# tappytap_6x6_connopposite.net
KiCad netlist of a schematic drawn in EAGLE
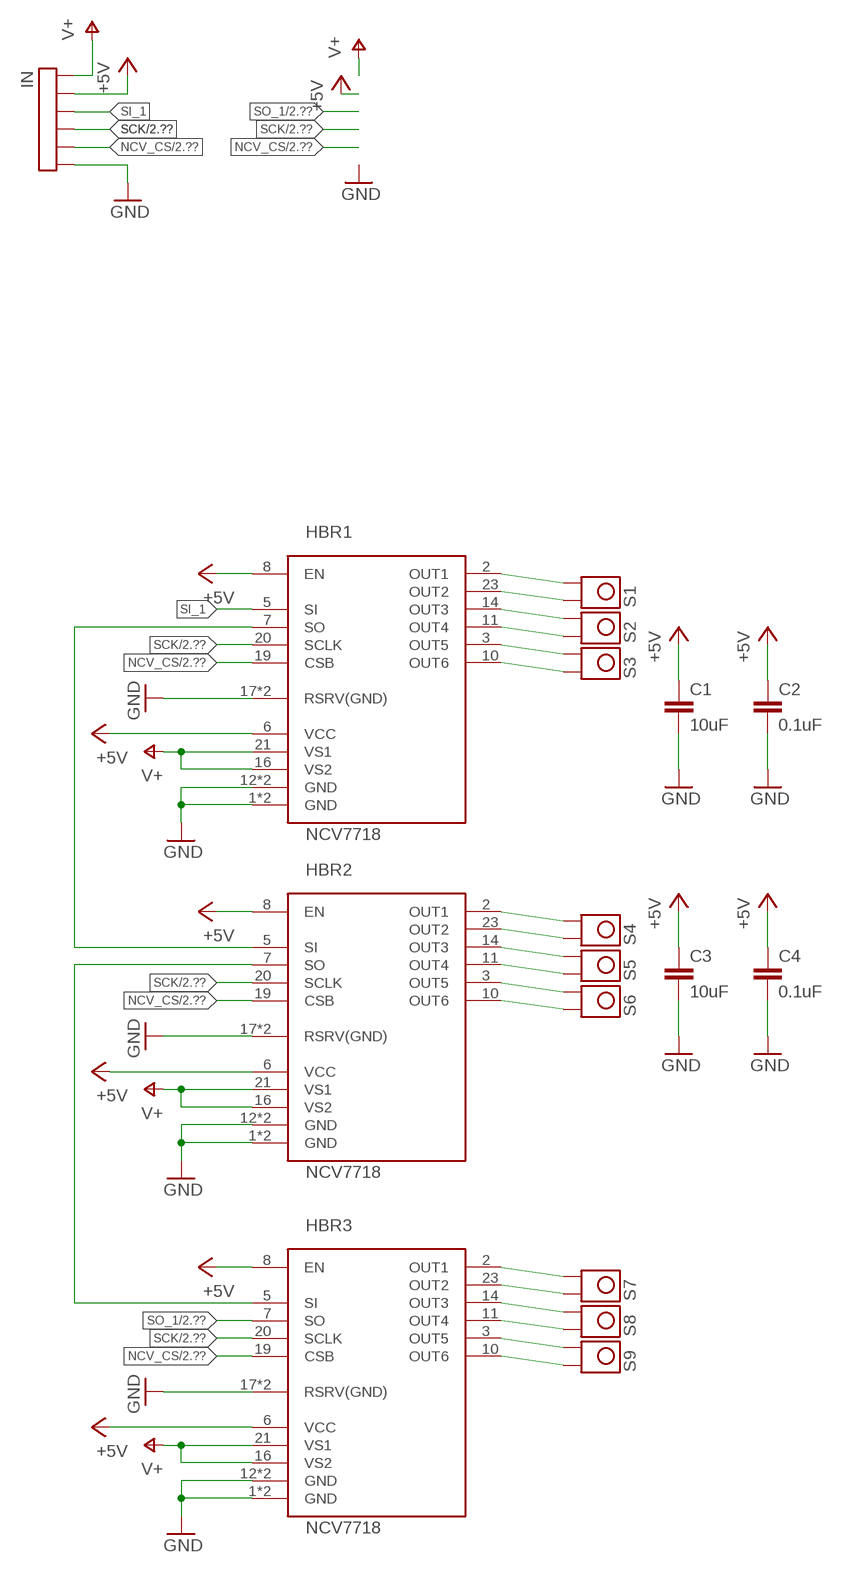
[diagram p0: schematic, sheet 1]
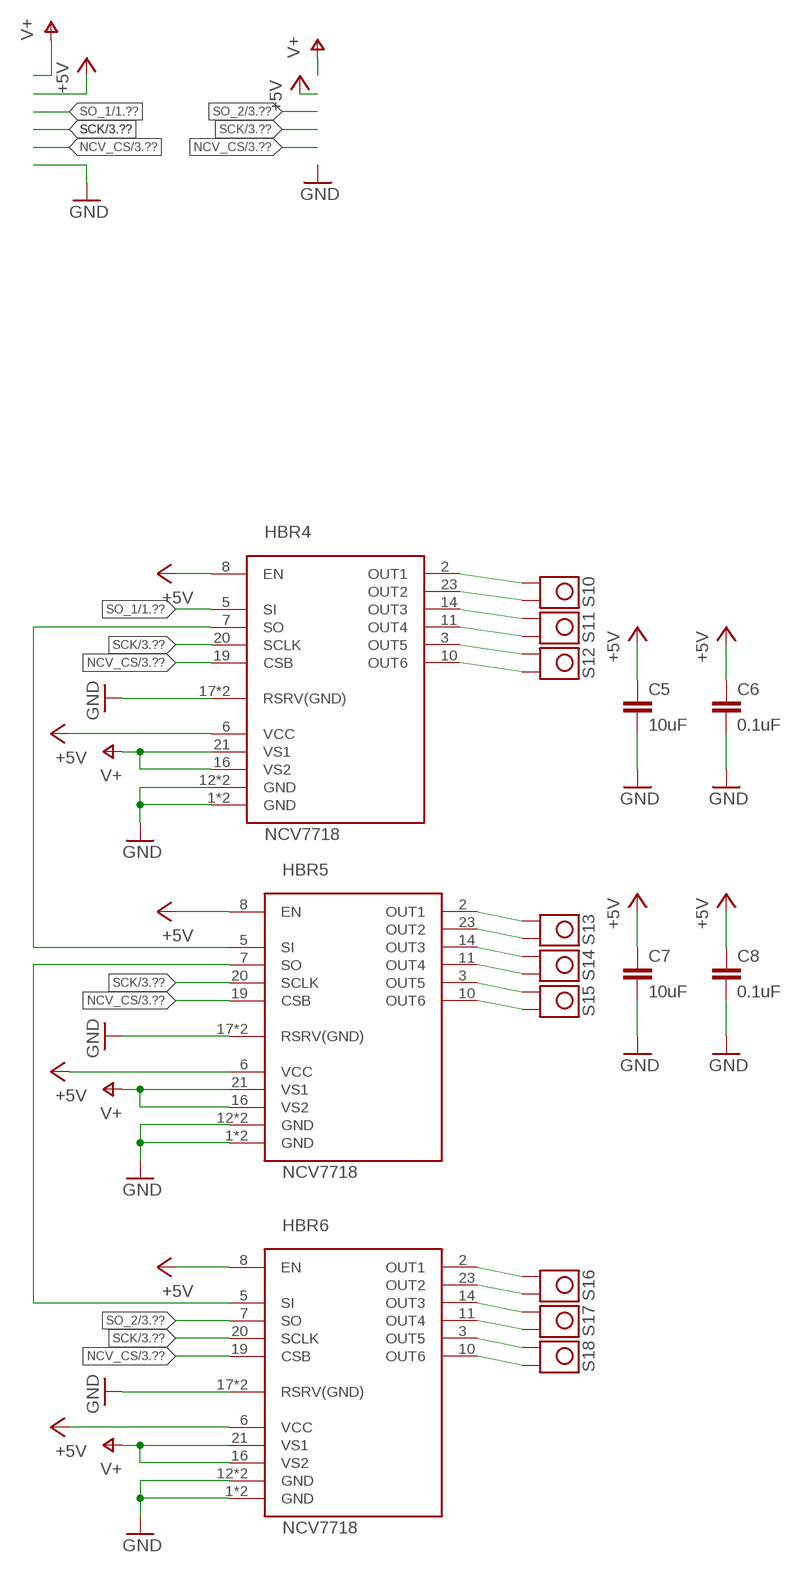
[diagram p1: schematic, sheet 2]
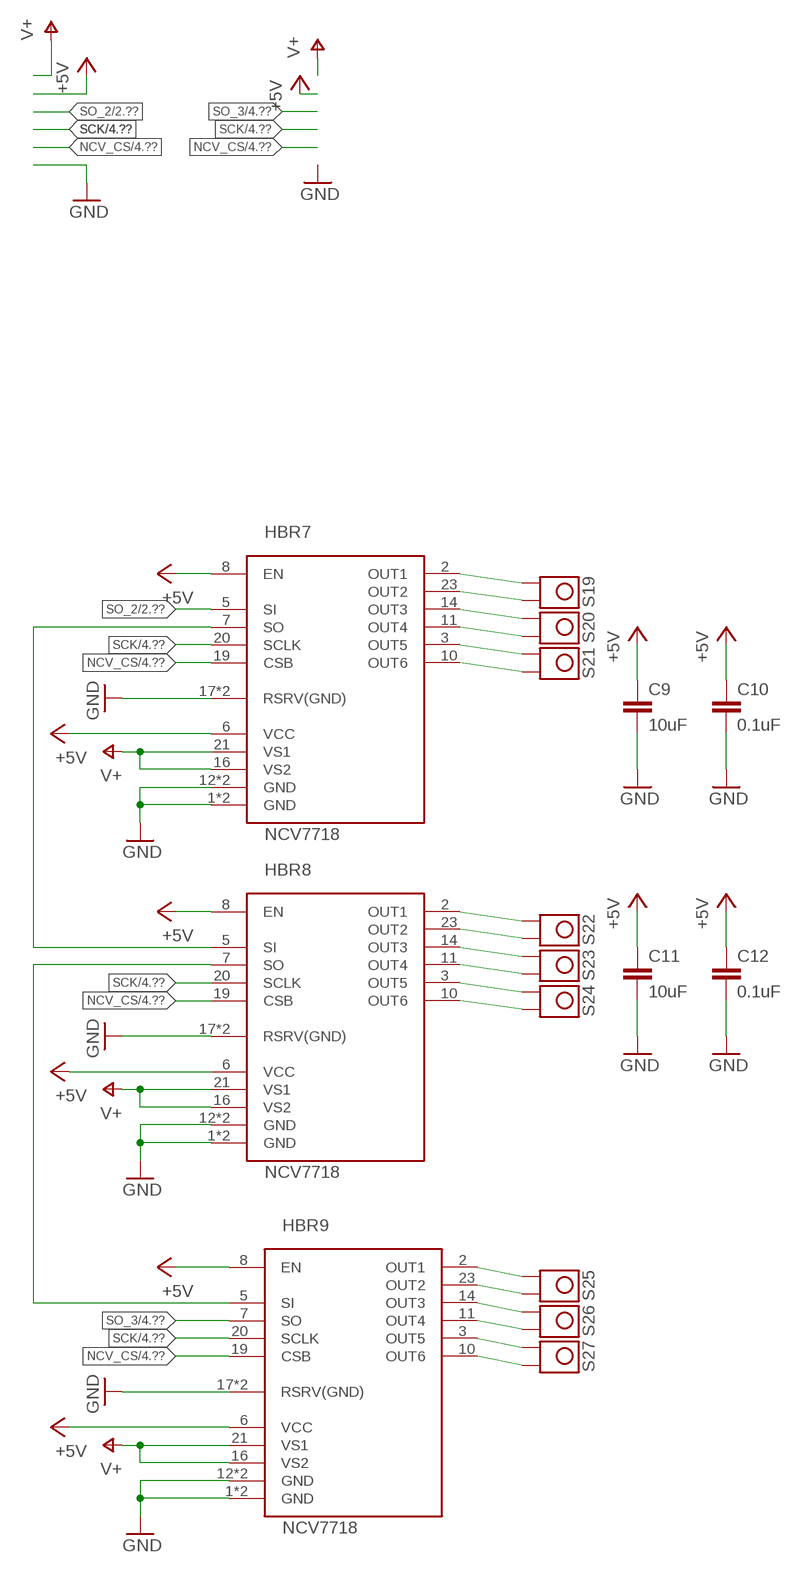
[diagram p2: schematic, sheet 3]
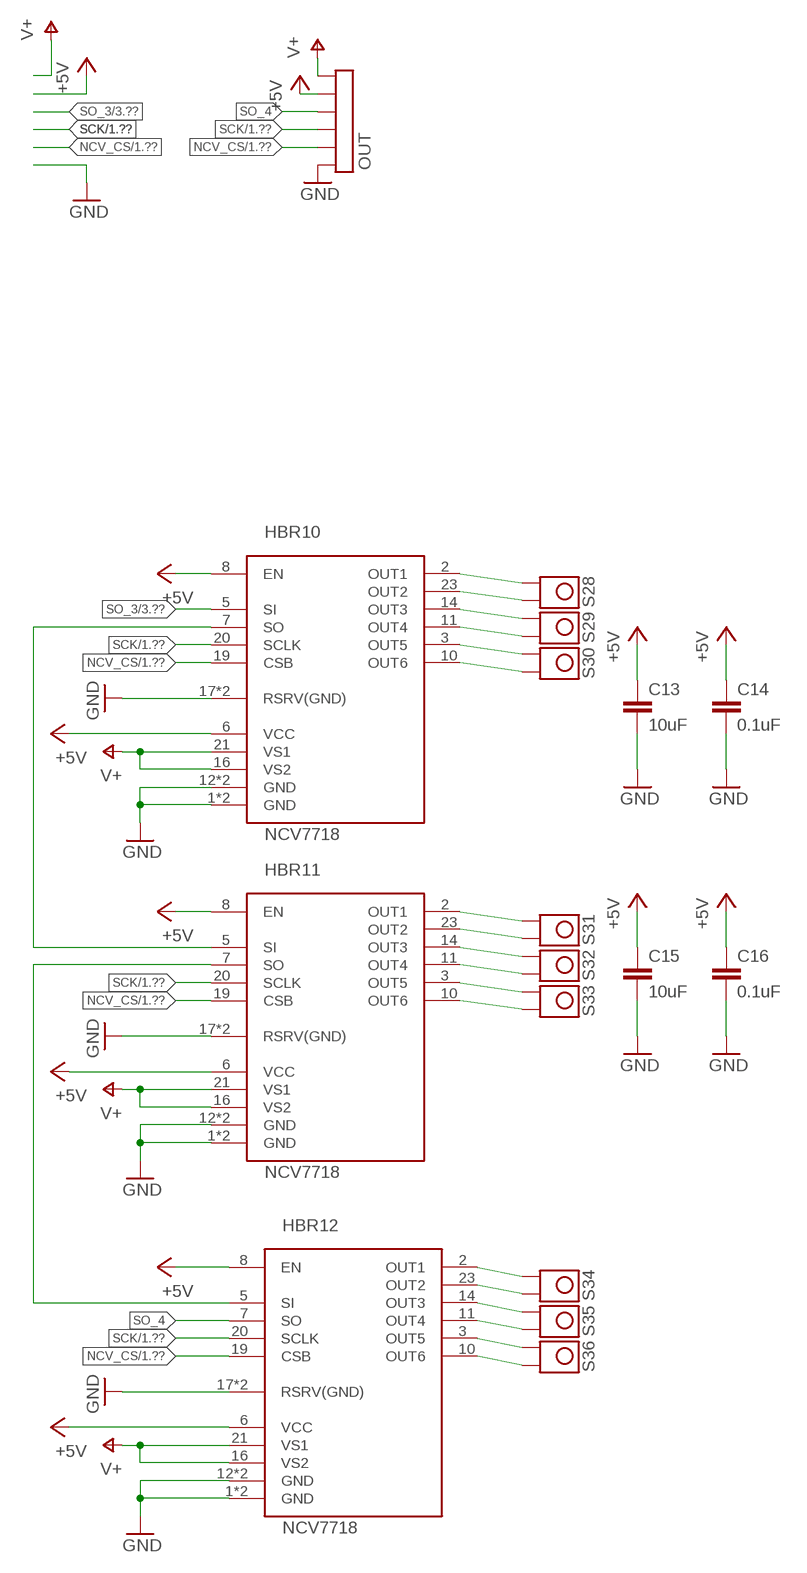
[diagram p3: schematic, sheet 4]

(export (version "E")
  (design (tool "Eeschema 10.0.6"))
  (components
    (comp (ref "C13")
      (value "10uF")
      (footprint "eagle-import:C0603")
      (libsource (lib "eagle-import") (part "C-EUC0603"))
    )
    (comp (ref "C14")
      (value "0.1uF")
      (footprint "eagle-import:C0603")
      (libsource (lib "eagle-import") (part "C-EUC0603"))
    )
    (comp (ref "C15")
      (value "10uF")
      (footprint "eagle-import:C0603")
      (libsource (lib "eagle-import") (part "C-EUC0603"))
    )
    (comp (ref "C16")
      (value "0.1uF")
      (footprint "eagle-import:C0603")
      (libsource (lib "eagle-import") (part "C-EUC0603"))
    )
    (comp (ref "HBR10")
      (value "NCV7718")
      (footprint "eagle-import:SSOP-24")
      (libsource (lib "eagle-import") (part "NCV7718"))
    )
    (comp (ref "HBR11")
      (value "NCV7718")
      (footprint "eagle-import:SSOP-24")
      (libsource (lib "eagle-import") (part "NCV7718"))
    )
    (comp (ref "HBR12")
      (value "NCV7718")
      (footprint "eagle-import:SSOP-24")
      (libsource (lib "eagle-import") (part "NCV7718"))
    )
    (comp (ref "OUT")
      (value "TP6")
      (footprint "eagle-import:TP6_2MM")
      (libsource (lib "eagle-import") (part "TP6"))
    )
    (comp (ref "S28")
      (value "TP_6MM_BIG_PAD")
      (footprint "eagle-import:TP_6MM_BIG_PAD")
      (libsource (lib "eagle-import") (part "TP_6MM_BIG_PAD"))
    )
    (comp (ref "S29")
      (value "TP_6MM_BIG_PAD")
      (footprint "eagle-import:TP_6MM_BIG_PAD")
      (libsource (lib "eagle-import") (part "TP_6MM_BIG_PAD"))
    )
    (comp (ref "S30")
      (value "TP_6MM_BIG_PAD")
      (footprint "eagle-import:TP_6MM_BIG_PAD")
      (libsource (lib "eagle-import") (part "TP_6MM_BIG_PAD"))
    )
    (comp (ref "S31")
      (value "TP_6MM_BIG_PAD")
      (footprint "eagle-import:TP_6MM_BIG_PAD")
      (libsource (lib "eagle-import") (part "TP_6MM_BIG_PAD"))
    )
    (comp (ref "S32")
      (value "TP_6MM_BIG_PAD")
      (footprint "eagle-import:TP_6MM_BIG_PAD")
      (libsource (lib "eagle-import") (part "TP_6MM_BIG_PAD"))
    )
    (comp (ref "S33")
      (value "TP_6MM_BIG_PAD")
      (footprint "eagle-import:TP_6MM_BIG_PAD")
      (libsource (lib "eagle-import") (part "TP_6MM_BIG_PAD"))
    )
    (comp (ref "S34")
      (value "TP_6MM_BIG_PAD")
      (footprint "eagle-import:TP_6MM_BIG_PAD")
      (libsource (lib "eagle-import") (part "TP_6MM_BIG_PAD"))
    )
    (comp (ref "S35")
      (value "TP_6MM_BIG_PAD")
      (footprint "eagle-import:TP_6MM_BIG_PAD")
      (libsource (lib "eagle-import") (part "TP_6MM_BIG_PAD"))
    )
    (comp (ref "S36")
      (value "TP_6MM_BIG_PAD")
      (footprint "eagle-import:TP_6MM_BIG_PAD")
      (libsource (lib "eagle-import") (part "TP_6MM_BIG_PAD"))
    )
    (comp (ref "C9")
      (value "10uF")
      (footprint "eagle-import:C0603")
      (libsource (lib "eagle-import") (part "C-EUC0603"))
    )
    (comp (ref "C10")
      (value "0.1uF")
      (footprint "eagle-import:C0603")
      (libsource (lib "eagle-import") (part "C-EUC0603"))
    )
    (comp (ref "C11")
      (value "10uF")
      (footprint "eagle-import:C0603")
      (libsource (lib "eagle-import") (part "C-EUC0603"))
    )
    (comp (ref "C12")
      (value "0.1uF")
      (footprint "eagle-import:C0603")
      (libsource (lib "eagle-import") (part "C-EUC0603"))
    )
    (comp (ref "HBR7")
      (value "NCV7718")
      (footprint "eagle-import:SSOP-24")
      (libsource (lib "eagle-import") (part "NCV7718"))
    )
    (comp (ref "HBR8")
      (value "NCV7718")
      (footprint "eagle-import:SSOP-24")
      (libsource (lib "eagle-import") (part "NCV7718"))
    )
    (comp (ref "HBR9")
      (value "NCV7718")
      (footprint "eagle-import:SSOP-24")
      (libsource (lib "eagle-import") (part "NCV7718"))
    )
    (comp (ref "S19")
      (value "TP_6MM_BIG_PAD")
      (footprint "eagle-import:TP_6MM_BIG_PAD")
      (libsource (lib "eagle-import") (part "TP_6MM_BIG_PAD"))
    )
    (comp (ref "S20")
      (value "TP_6MM_BIG_PAD")
      (footprint "eagle-import:TP_6MM_BIG_PAD")
      (libsource (lib "eagle-import") (part "TP_6MM_BIG_PAD"))
    )
    (comp (ref "S21")
      (value "TP_6MM_BIG_PAD")
      (footprint "eagle-import:TP_6MM_BIG_PAD")
      (libsource (lib "eagle-import") (part "TP_6MM_BIG_PAD"))
    )
    (comp (ref "S22")
      (value "TP_6MM_BIG_PAD")
      (footprint "eagle-import:TP_6MM_BIG_PAD")
      (libsource (lib "eagle-import") (part "TP_6MM_BIG_PAD"))
    )
    (comp (ref "S23")
      (value "TP_6MM_BIG_PAD")
      (footprint "eagle-import:TP_6MM_BIG_PAD")
      (libsource (lib "eagle-import") (part "TP_6MM_BIG_PAD"))
    )
    (comp (ref "S24")
      (value "TP_6MM_BIG_PAD")
      (footprint "eagle-import:TP_6MM_BIG_PAD")
      (libsource (lib "eagle-import") (part "TP_6MM_BIG_PAD"))
    )
    (comp (ref "S25")
      (value "TP_6MM_BIG_PAD")
      (footprint "eagle-import:TP_6MM_BIG_PAD")
      (libsource (lib "eagle-import") (part "TP_6MM_BIG_PAD"))
    )
    (comp (ref "S26")
      (value "TP_6MM_BIG_PAD")
      (footprint "eagle-import:TP_6MM_BIG_PAD")
      (libsource (lib "eagle-import") (part "TP_6MM_BIG_PAD"))
    )
    (comp (ref "S27")
      (value "TP_6MM_BIG_PAD")
      (footprint "eagle-import:TP_6MM_BIG_PAD")
      (libsource (lib "eagle-import") (part "TP_6MM_BIG_PAD"))
    )
    (comp (ref "C1")
      (value "10uF")
      (footprint "eagle-import:C0603")
      (libsource (lib "eagle-import") (part "C-EUC0603"))
    )
    (comp (ref "C2")
      (value "0.1uF")
      (footprint "eagle-import:C0603")
      (libsource (lib "eagle-import") (part "C-EUC0603"))
    )
    (comp (ref "C3")
      (value "10uF")
      (footprint "eagle-import:C0603")
      (libsource (lib "eagle-import") (part "C-EUC0603"))
    )
    (comp (ref "C4")
      (value "0.1uF")
      (footprint "eagle-import:C0603")
      (libsource (lib "eagle-import") (part "C-EUC0603"))
    )
    (comp (ref "HBR1")
      (value "NCV7718")
      (footprint "eagle-import:SSOP-24")
      (libsource (lib "eagle-import") (part "NCV7718"))
    )
    (comp (ref "HBR2")
      (value "NCV7718")
      (footprint "eagle-import:SSOP-24")
      (libsource (lib "eagle-import") (part "NCV7718"))
    )
    (comp (ref "HBR3")
      (value "NCV7718")
      (footprint "eagle-import:SSOP-24")
      (libsource (lib "eagle-import") (part "NCV7718"))
    )
    (comp (ref "IN")
      (value "TP6")
      (footprint "eagle-import:TP6_2MM")
      (libsource (lib "eagle-import") (part "TP6"))
    )
    (comp (ref "S1")
      (value "TP_6MM_BIG_PAD")
      (footprint "eagle-import:TP_6MM_BIG_PAD")
      (libsource (lib "eagle-import") (part "TP_6MM_BIG_PAD"))
    )
    (comp (ref "S2")
      (value "TP_6MM_BIG_PAD")
      (footprint "eagle-import:TP_6MM_BIG_PAD")
      (libsource (lib "eagle-import") (part "TP_6MM_BIG_PAD"))
    )
    (comp (ref "S3")
      (value "TP_6MM_BIG_PAD")
      (footprint "eagle-import:TP_6MM_BIG_PAD")
      (libsource (lib "eagle-import") (part "TP_6MM_BIG_PAD"))
    )
    (comp (ref "S4")
      (value "TP_6MM_BIG_PAD")
      (footprint "eagle-import:TP_6MM_BIG_PAD")
      (libsource (lib "eagle-import") (part "TP_6MM_BIG_PAD"))
    )
    (comp (ref "S5")
      (value "TP_6MM_BIG_PAD")
      (footprint "eagle-import:TP_6MM_BIG_PAD")
      (libsource (lib "eagle-import") (part "TP_6MM_BIG_PAD"))
    )
    (comp (ref "S6")
      (value "TP_6MM_BIG_PAD")
      (footprint "eagle-import:TP_6MM_BIG_PAD")
      (libsource (lib "eagle-import") (part "TP_6MM_BIG_PAD"))
    )
    (comp (ref "S7")
      (value "TP_6MM_BIG_PAD")
      (footprint "eagle-import:TP_6MM_BIG_PAD")
      (libsource (lib "eagle-import") (part "TP_6MM_BIG_PAD"))
    )
    (comp (ref "S8")
      (value "TP_6MM_BIG_PAD")
      (footprint "eagle-import:TP_6MM_BIG_PAD")
      (libsource (lib "eagle-import") (part "TP_6MM_BIG_PAD"))
    )
    (comp (ref "S9")
      (value "TP_6MM_BIG_PAD")
      (footprint "eagle-import:TP_6MM_BIG_PAD")
      (libsource (lib "eagle-import") (part "TP_6MM_BIG_PAD"))
    )
    (comp (ref "C5")
      (value "10uF")
      (footprint "eagle-import:C0603")
      (libsource (lib "eagle-import") (part "C-EUC0603"))
    )
    (comp (ref "C6")
      (value "0.1uF")
      (footprint "eagle-import:C0603")
      (libsource (lib "eagle-import") (part "C-EUC0603"))
    )
    (comp (ref "C7")
      (value "10uF")
      (footprint "eagle-import:C0603")
      (libsource (lib "eagle-import") (part "C-EUC0603"))
    )
    (comp (ref "C8")
      (value "0.1uF")
      (footprint "eagle-import:C0603")
      (libsource (lib "eagle-import") (part "C-EUC0603"))
    )
    (comp (ref "HBR4")
      (value "NCV7718")
      (footprint "eagle-import:SSOP-24")
      (libsource (lib "eagle-import") (part "NCV7718"))
    )
    (comp (ref "HBR5")
      (value "NCV7718")
      (footprint "eagle-import:SSOP-24")
      (libsource (lib "eagle-import") (part "NCV7718"))
    )
    (comp (ref "HBR6")
      (value "NCV7718")
      (footprint "eagle-import:SSOP-24")
      (libsource (lib "eagle-import") (part "NCV7718"))
    )
    (comp (ref "S10")
      (value "TP_6MM_BIG_PAD")
      (footprint "eagle-import:TP_6MM_BIG_PAD")
      (libsource (lib "eagle-import") (part "TP_6MM_BIG_PAD"))
    )
    (comp (ref "S11")
      (value "TP_6MM_BIG_PAD")
      (footprint "eagle-import:TP_6MM_BIG_PAD")
      (libsource (lib "eagle-import") (part "TP_6MM_BIG_PAD"))
    )
    (comp (ref "S12")
      (value "TP_6MM_BIG_PAD")
      (footprint "eagle-import:TP_6MM_BIG_PAD")
      (libsource (lib "eagle-import") (part "TP_6MM_BIG_PAD"))
    )
    (comp (ref "S13")
      (value "TP_6MM_BIG_PAD")
      (footprint "eagle-import:TP_6MM_BIG_PAD")
      (libsource (lib "eagle-import") (part "TP_6MM_BIG_PAD"))
    )
    (comp (ref "S14")
      (value "TP_6MM_BIG_PAD")
      (footprint "eagle-import:TP_6MM_BIG_PAD")
      (libsource (lib "eagle-import") (part "TP_6MM_BIG_PAD"))
    )
    (comp (ref "S15")
      (value "TP_6MM_BIG_PAD")
      (footprint "eagle-import:TP_6MM_BIG_PAD")
      (libsource (lib "eagle-import") (part "TP_6MM_BIG_PAD"))
    )
    (comp (ref "S16")
      (value "TP_6MM_BIG_PAD")
      (footprint "eagle-import:TP_6MM_BIG_PAD")
      (libsource (lib "eagle-import") (part "TP_6MM_BIG_PAD"))
    )
    (comp (ref "S17")
      (value "TP_6MM_BIG_PAD")
      (footprint "eagle-import:TP_6MM_BIG_PAD")
      (libsource (lib "eagle-import") (part "TP_6MM_BIG_PAD"))
    )
    (comp (ref "S18")
      (value "TP_6MM_BIG_PAD")
      (footprint "eagle-import:TP_6MM_BIG_PAD")
      (libsource (lib "eagle-import") (part "TP_6MM_BIG_PAD"))
    )
  )
  (nets
    (net (code "1") (name "+5V") (class "Default")
      (node (ref "C1") (pin "1") (pinfunction "1_1") (pintype "passive"))
      (node (ref "C10") (pin "1") (pinfunction "1_1") (pintype "passive"))
      (node (ref "C11") (pin "1") (pinfunction "1_1") (pintype "passive"))
      (node (ref "C12") (pin "1") (pinfunction "1_1") (pintype "passive"))
      (node (ref "C13") (pin "1") (pinfunction "1_1") (pintype "passive"))
      (node (ref "C14") (pin "1") (pinfunction "1_1") (pintype "passive"))
      (node (ref "C15") (pin "1") (pinfunction "1_1") (pintype "passive"))
      (node (ref "C16") (pin "1") (pinfunction "1_1") (pintype "passive"))
      (node (ref "C2") (pin "1") (pinfunction "1_1") (pintype "passive"))
      (node (ref "C3") (pin "1") (pinfunction "1_1") (pintype "passive"))
      (node (ref "C4") (pin "1") (pinfunction "1_1") (pintype "passive"))
      (node (ref "C5") (pin "1") (pinfunction "1_1") (pintype "passive"))
      (node (ref "C6") (pin "1") (pinfunction "1_1") (pintype "passive"))
      (node (ref "C7") (pin "1") (pinfunction "1_1") (pintype "passive"))
      (node (ref "C8") (pin "1") (pinfunction "1_1") (pintype "passive"))
      (node (ref "C9") (pin "1") (pinfunction "1_1") (pintype "passive"))
      (node (ref "HBR1") (pin "6") (pinfunction "VCC_6") (pintype "bidirectional"))
      (node (ref "HBR1") (pin "8") (pinfunction "EN_8") (pintype "bidirectional"))
      (node (ref "HBR10") (pin "6") (pinfunction "VCC_6") (pintype "bidirectional"))
      (node (ref "HBR10") (pin "8") (pinfunction "EN_8") (pintype "bidirectional"))
      (node (ref "HBR11") (pin "6") (pinfunction "VCC_6") (pintype "bidirectional"))
      (node (ref "HBR11") (pin "8") (pinfunction "EN_8") (pintype "bidirectional"))
      (node (ref "HBR12") (pin "6") (pinfunction "VCC_6") (pintype "bidirectional"))
      (node (ref "HBR12") (pin "8") (pinfunction "EN_8") (pintype "bidirectional"))
      (node (ref "HBR2") (pin "6") (pinfunction "VCC_6") (pintype "bidirectional"))
      (node (ref "HBR2") (pin "8") (pinfunction "EN_8") (pintype "bidirectional"))
      (node (ref "HBR3") (pin "6") (pinfunction "VCC_6") (pintype "bidirectional"))
      (node (ref "HBR3") (pin "8") (pinfunction "EN_8") (pintype "bidirectional"))
      (node (ref "HBR4") (pin "6") (pinfunction "VCC_6") (pintype "bidirectional"))
      (node (ref "HBR4") (pin "8") (pinfunction "EN_8") (pintype "bidirectional"))
      (node (ref "HBR5") (pin "6") (pinfunction "VCC_6") (pintype "bidirectional"))
      (node (ref "HBR5") (pin "8") (pinfunction "EN_8") (pintype "bidirectional"))
      (node (ref "HBR6") (pin "6") (pinfunction "VCC_6") (pintype "bidirectional"))
      (node (ref "HBR6") (pin "8") (pinfunction "EN_8") (pintype "bidirectional"))
      (node (ref "HBR7") (pin "6") (pinfunction "VCC_6") (pintype "bidirectional"))
      (node (ref "HBR7") (pin "8") (pinfunction "EN_8") (pintype "bidirectional"))
      (node (ref "HBR8") (pin "6") (pinfunction "VCC_6") (pintype "bidirectional"))
      (node (ref "HBR8") (pin "8") (pinfunction "EN_8") (pintype "bidirectional"))
      (node (ref "HBR9") (pin "6") (pinfunction "VCC_6") (pintype "bidirectional"))
      (node (ref "HBR9") (pin "8") (pinfunction "EN_8") (pintype "bidirectional"))
      (node (ref "IN") (pin "P$5") (pinfunction "5_P$5") (pintype "bidirectional"))
      (node (ref "OUT") (pin "P$2") (pinfunction "2_P$2") (pintype "bidirectional"))
    )
    (net (code "2") (name "GND") (class "Default")
      (node (ref "C1") (pin "2") (pinfunction "2_2") (pintype "passive"))
      (node (ref "C10") (pin "2") (pinfunction "2_2") (pintype "passive"))
      (node (ref "C11") (pin "2") (pinfunction "2_2") (pintype "passive"))
      (node (ref "C12") (pin "2") (pinfunction "2_2") (pintype "passive"))
      (node (ref "C13") (pin "2") (pinfunction "2_2") (pintype "passive"))
      (node (ref "C14") (pin "2") (pinfunction "2_2") (pintype "passive"))
      (node (ref "C15") (pin "2") (pinfunction "2_2") (pintype "passive"))
      (node (ref "C16") (pin "2") (pinfunction "2_2") (pintype "passive"))
      (node (ref "C2") (pin "2") (pinfunction "2_2") (pintype "passive"))
      (node (ref "C3") (pin "2") (pinfunction "2_2") (pintype "passive"))
      (node (ref "C4") (pin "2") (pinfunction "2_2") (pintype "passive"))
      (node (ref "C5") (pin "2") (pinfunction "2_2") (pintype "passive"))
      (node (ref "C6") (pin "2") (pinfunction "2_2") (pintype "passive"))
      (node (ref "C7") (pin "2") (pinfunction "2_2") (pintype "passive"))
      (node (ref "C8") (pin "2") (pinfunction "2_2") (pintype "passive"))
      (node (ref "C9") (pin "2") (pinfunction "2_2") (pintype "passive"))
      (node (ref "HBR1") (pin "1") (pinfunction "GND_1") (pintype "bidirectional"))
      (node (ref "HBR1") (pin "12") (pinfunction "GND_12") (pintype "bidirectional"))
      (node (ref "HBR1") (pin "13") (pinfunction "GND_13") (pintype "bidirectional"))
      (node (ref "HBR1") (pin "17") (pinfunction "RSRV(GND)_17") (pintype "bidirectional"))
      (node (ref "HBR1") (pin "18") (pinfunction "RSRV(GND)_18") (pintype "bidirectional"))
      (node (ref "HBR1") (pin "24") (pinfunction "GND_24") (pintype "bidirectional"))
      (node (ref "HBR10") (pin "1") (pinfunction "GND_1") (pintype "bidirectional"))
      (node (ref "HBR10") (pin "12") (pinfunction "GND_12") (pintype "bidirectional"))
      (node (ref "HBR10") (pin "13") (pinfunction "GND_13") (pintype "bidirectional"))
      (node (ref "HBR10") (pin "17") (pinfunction "RSRV(GND)_17") (pintype "bidirectional"))
      (node (ref "HBR10") (pin "18") (pinfunction "RSRV(GND)_18") (pintype "bidirectional"))
      (node (ref "HBR10") (pin "24") (pinfunction "GND_24") (pintype "bidirectional"))
      (node (ref "HBR11") (pin "1") (pinfunction "GND_1") (pintype "bidirectional"))
      (node (ref "HBR11") (pin "12") (pinfunction "GND_12") (pintype "bidirectional"))
      (node (ref "HBR11") (pin "13") (pinfunction "GND_13") (pintype "bidirectional"))
      (node (ref "HBR11") (pin "17") (pinfunction "RSRV(GND)_17") (pintype "bidirectional"))
      (node (ref "HBR11") (pin "18") (pinfunction "RSRV(GND)_18") (pintype "bidirectional"))
      (node (ref "HBR11") (pin "24") (pinfunction "GND_24") (pintype "bidirectional"))
      (node (ref "HBR12") (pin "1") (pinfunction "GND_1") (pintype "bidirectional"))
      (node (ref "HBR12") (pin "12") (pinfunction "GND_12") (pintype "bidirectional"))
      (node (ref "HBR12") (pin "13") (pinfunction "GND_13") (pintype "bidirectional"))
      (node (ref "HBR12") (pin "17") (pinfunction "RSRV(GND)_17") (pintype "bidirectional"))
      (node (ref "HBR12") (pin "18") (pinfunction "RSRV(GND)_18") (pintype "bidirectional"))
      (node (ref "HBR12") (pin "24") (pinfunction "GND_24") (pintype "bidirectional"))
      (node (ref "HBR2") (pin "1") (pinfunction "GND_1") (pintype "bidirectional"))
      (node (ref "HBR2") (pin "12") (pinfunction "GND_12") (pintype "bidirectional"))
      (node (ref "HBR2") (pin "13") (pinfunction "GND_13") (pintype "bidirectional"))
      (node (ref "HBR2") (pin "17") (pinfunction "RSRV(GND)_17") (pintype "bidirectional"))
      (node (ref "HBR2") (pin "18") (pinfunction "RSRV(GND)_18") (pintype "bidirectional"))
      (node (ref "HBR2") (pin "24") (pinfunction "GND_24") (pintype "bidirectional"))
      (node (ref "HBR3") (pin "1") (pinfunction "GND_1") (pintype "bidirectional"))
      (node (ref "HBR3") (pin "12") (pinfunction "GND_12") (pintype "bidirectional"))
      (node (ref "HBR3") (pin "13") (pinfunction "GND_13") (pintype "bidirectional"))
      (node (ref "HBR3") (pin "17") (pinfunction "RSRV(GND)_17") (pintype "bidirectional"))
      (node (ref "HBR3") (pin "18") (pinfunction "RSRV(GND)_18") (pintype "bidirectional"))
      (node (ref "HBR3") (pin "24") (pinfunction "GND_24") (pintype "bidirectional"))
      (node (ref "HBR4") (pin "1") (pinfunction "GND_1") (pintype "bidirectional"))
      (node (ref "HBR4") (pin "12") (pinfunction "GND_12") (pintype "bidirectional"))
      (node (ref "HBR4") (pin "13") (pinfunction "GND_13") (pintype "bidirectional"))
      (node (ref "HBR4") (pin "17") (pinfunction "RSRV(GND)_17") (pintype "bidirectional"))
      (node (ref "HBR4") (pin "18") (pinfunction "RSRV(GND)_18") (pintype "bidirectional"))
      (node (ref "HBR4") (pin "24") (pinfunction "GND_24") (pintype "bidirectional"))
      (node (ref "HBR5") (pin "1") (pinfunction "GND_1") (pintype "bidirectional"))
      (node (ref "HBR5") (pin "12") (pinfunction "GND_12") (pintype "bidirectional"))
      (node (ref "HBR5") (pin "13") (pinfunction "GND_13") (pintype "bidirectional"))
      (node (ref "HBR5") (pin "17") (pinfunction "RSRV(GND)_17") (pintype "bidirectional"))
      (node (ref "HBR5") (pin "18") (pinfunction "RSRV(GND)_18") (pintype "bidirectional"))
      (node (ref "HBR5") (pin "24") (pinfunction "GND_24") (pintype "bidirectional"))
      (node (ref "HBR6") (pin "1") (pinfunction "GND_1") (pintype "bidirectional"))
      (node (ref "HBR6") (pin "12") (pinfunction "GND_12") (pintype "bidirectional"))
      (node (ref "HBR6") (pin "13") (pinfunction "GND_13") (pintype "bidirectional"))
      (node (ref "HBR6") (pin "17") (pinfunction "RSRV(GND)_17") (pintype "bidirectional"))
      (node (ref "HBR6") (pin "18") (pinfunction "RSRV(GND)_18") (pintype "bidirectional"))
      (node (ref "HBR6") (pin "24") (pinfunction "GND_24") (pintype "bidirectional"))
      (node (ref "HBR7") (pin "1") (pinfunction "GND_1") (pintype "bidirectional"))
      (node (ref "HBR7") (pin "12") (pinfunction "GND_12") (pintype "bidirectional"))
      (node (ref "HBR7") (pin "13") (pinfunction "GND_13") (pintype "bidirectional"))
      (node (ref "HBR7") (pin "17") (pinfunction "RSRV(GND)_17") (pintype "bidirectional"))
      (node (ref "HBR7") (pin "18") (pinfunction "RSRV(GND)_18") (pintype "bidirectional"))
      (node (ref "HBR7") (pin "24") (pinfunction "GND_24") (pintype "bidirectional"))
      (node (ref "HBR8") (pin "1") (pinfunction "GND_1") (pintype "bidirectional"))
      (node (ref "HBR8") (pin "12") (pinfunction "GND_12") (pintype "bidirectional"))
      (node (ref "HBR8") (pin "13") (pinfunction "GND_13") (pintype "bidirectional"))
      (node (ref "HBR8") (pin "17") (pinfunction "RSRV(GND)_17") (pintype "bidirectional"))
      (node (ref "HBR8") (pin "18") (pinfunction "RSRV(GND)_18") (pintype "bidirectional"))
      (node (ref "HBR8") (pin "24") (pinfunction "GND_24") (pintype "bidirectional"))
      (node (ref "HBR9") (pin "1") (pinfunction "GND_1") (pintype "bidirectional"))
      (node (ref "HBR9") (pin "12") (pinfunction "GND_12") (pintype "bidirectional"))
      (node (ref "HBR9") (pin "13") (pinfunction "GND_13") (pintype "bidirectional"))
      (node (ref "HBR9") (pin "17") (pinfunction "RSRV(GND)_17") (pintype "bidirectional"))
      (node (ref "HBR9") (pin "18") (pinfunction "RSRV(GND)_18") (pintype "bidirectional"))
      (node (ref "HBR9") (pin "24") (pinfunction "GND_24") (pintype "bidirectional"))
      (node (ref "IN") (pin "P$1") (pinfunction "1_P$1") (pintype "bidirectional"))
      (node (ref "OUT") (pin "P$6") (pinfunction "6_P$6") (pintype "bidirectional"))
    )
    (net (code "3") (name "NCV_CS") (class "Default")
      (node (ref "HBR1") (pin "19") (pinfunction "CSB_19") (pintype "bidirectional"))
      (node (ref "HBR10") (pin "19") (pinfunction "CSB_19") (pintype "bidirectional"))
      (node (ref "HBR11") (pin "19") (pinfunction "CSB_19") (pintype "bidirectional"))
      (node (ref "HBR12") (pin "19") (pinfunction "CSB_19") (pintype "bidirectional"))
      (node (ref "HBR2") (pin "19") (pinfunction "CSB_19") (pintype "bidirectional"))
      (node (ref "HBR3") (pin "19") (pinfunction "CSB_19") (pintype "bidirectional"))
      (node (ref "HBR4") (pin "19") (pinfunction "CSB_19") (pintype "bidirectional"))
      (node (ref "HBR5") (pin "19") (pinfunction "CSB_19") (pintype "bidirectional"))
      (node (ref "HBR6") (pin "19") (pinfunction "CSB_19") (pintype "bidirectional"))
      (node (ref "HBR7") (pin "19") (pinfunction "CSB_19") (pintype "bidirectional"))
      (node (ref "HBR8") (pin "19") (pinfunction "CSB_19") (pintype "bidirectional"))
      (node (ref "HBR9") (pin "19") (pinfunction "CSB_19") (pintype "bidirectional"))
      (node (ref "IN") (pin "P$2") (pinfunction "2_P$2") (pintype "bidirectional"))
      (node (ref "OUT") (pin "P$5") (pinfunction "5_P$5") (pintype "bidirectional"))
    )
    (net (code "4") (name "Net-(HBR1-OUT1)") (class "Default")
      (node (ref "HBR1") (pin "2") (pinfunction "OUT1_2") (pintype "bidirectional"))
      (node (ref "S1") (pin "P$1") (pinfunction "0_P$1") (pintype "bidirectional"))
    )
    (net (code "5") (name "Net-(HBR1-OUT2)") (class "Default")
      (node (ref "HBR1") (pin "23") (pinfunction "OUT2_23") (pintype "bidirectional"))
      (node (ref "S1") (pin "P$2") (pinfunction "1_P$2") (pintype "bidirectional"))
    )
    (net (code "6") (name "Net-(HBR1-OUT3)") (class "Default")
      (node (ref "HBR1") (pin "14") (pinfunction "OUT3_14") (pintype "bidirectional"))
      (node (ref "S2") (pin "P$1") (pinfunction "0_P$1") (pintype "bidirectional"))
    )
    (net (code "7") (name "Net-(HBR1-OUT4)") (class "Default")
      (node (ref "HBR1") (pin "11") (pinfunction "OUT4_11") (pintype "bidirectional"))
      (node (ref "S2") (pin "P$2") (pinfunction "1_P$2") (pintype "bidirectional"))
    )
    (net (code "8") (name "Net-(HBR1-OUT5)") (class "Default")
      (node (ref "HBR1") (pin "3") (pinfunction "OUT5_3") (pintype "bidirectional"))
      (node (ref "S3") (pin "P$1") (pinfunction "0_P$1") (pintype "bidirectional"))
    )
    (net (code "9") (name "Net-(HBR1-OUT6)") (class "Default")
      (node (ref "HBR1") (pin "10") (pinfunction "OUT6_10") (pintype "bidirectional"))
      (node (ref "S3") (pin "P$2") (pinfunction "1_P$2") (pintype "bidirectional"))
    )
    (net (code "10") (name "Net-(HBR1-SO)") (class "Default")
      (node (ref "HBR1") (pin "7") (pinfunction "SO_7") (pintype "bidirectional"))
      (node (ref "HBR2") (pin "5") (pinfunction "SI_5") (pintype "bidirectional"))
    )
    (net (code "11") (name "Net-(HBR2-OUT1)") (class "Default")
      (node (ref "HBR2") (pin "2") (pinfunction "OUT1_2") (pintype "bidirectional"))
      (node (ref "S4") (pin "P$1") (pinfunction "0_P$1") (pintype "bidirectional"))
    )
    (net (code "12") (name "Net-(HBR2-OUT2)") (class "Default")
      (node (ref "HBR2") (pin "23") (pinfunction "OUT2_23") (pintype "bidirectional"))
      (node (ref "S4") (pin "P$2") (pinfunction "1_P$2") (pintype "bidirectional"))
    )
    (net (code "13") (name "Net-(HBR2-OUT3)") (class "Default")
      (node (ref "HBR2") (pin "14") (pinfunction "OUT3_14") (pintype "bidirectional"))
      (node (ref "S5") (pin "P$1") (pinfunction "0_P$1") (pintype "bidirectional"))
    )
    (net (code "14") (name "Net-(HBR2-OUT4)") (class "Default")
      (node (ref "HBR2") (pin "11") (pinfunction "OUT4_11") (pintype "bidirectional"))
      (node (ref "S5") (pin "P$2") (pinfunction "1_P$2") (pintype "bidirectional"))
    )
    (net (code "15") (name "Net-(HBR2-OUT5)") (class "Default")
      (node (ref "HBR2") (pin "3") (pinfunction "OUT5_3") (pintype "bidirectional"))
      (node (ref "S6") (pin "P$1") (pinfunction "0_P$1") (pintype "bidirectional"))
    )
    (net (code "16") (name "Net-(HBR2-OUT6)") (class "Default")
      (node (ref "HBR2") (pin "10") (pinfunction "OUT6_10") (pintype "bidirectional"))
      (node (ref "S6") (pin "P$2") (pinfunction "1_P$2") (pintype "bidirectional"))
    )
    (net (code "17") (name "Net-(HBR2-SO)") (class "Default")
      (node (ref "HBR2") (pin "7") (pinfunction "SO_7") (pintype "bidirectional"))
      (node (ref "HBR3") (pin "5") (pinfunction "SI_5") (pintype "bidirectional"))
    )
    (net (code "18") (name "Net-(HBR3-OUT1)") (class "Default")
      (node (ref "HBR3") (pin "2") (pinfunction "OUT1_2") (pintype "bidirectional"))
      (node (ref "S7") (pin "P$1") (pinfunction "0_P$1") (pintype "bidirectional"))
    )
    (net (code "19") (name "Net-(HBR3-OUT2)") (class "Default")
      (node (ref "HBR3") (pin "23") (pinfunction "OUT2_23") (pintype "bidirectional"))
      (node (ref "S7") (pin "P$2") (pinfunction "1_P$2") (pintype "bidirectional"))
    )
    (net (code "20") (name "Net-(HBR3-OUT3)") (class "Default")
      (node (ref "HBR3") (pin "14") (pinfunction "OUT3_14") (pintype "bidirectional"))
      (node (ref "S8") (pin "P$1") (pinfunction "0_P$1") (pintype "bidirectional"))
    )
    (net (code "21") (name "Net-(HBR3-OUT4)") (class "Default")
      (node (ref "HBR3") (pin "11") (pinfunction "OUT4_11") (pintype "bidirectional"))
      (node (ref "S8") (pin "P$2") (pinfunction "1_P$2") (pintype "bidirectional"))
    )
    (net (code "22") (name "Net-(HBR3-OUT5)") (class "Default")
      (node (ref "HBR3") (pin "3") (pinfunction "OUT5_3") (pintype "bidirectional"))
      (node (ref "S9") (pin "P$1") (pinfunction "0_P$1") (pintype "bidirectional"))
    )
    (net (code "23") (name "Net-(HBR3-OUT6)") (class "Default")
      (node (ref "HBR3") (pin "10") (pinfunction "OUT6_10") (pintype "bidirectional"))
      (node (ref "S9") (pin "P$2") (pinfunction "1_P$2") (pintype "bidirectional"))
    )
    (net (code "24") (name "Net-(HBR4-OUT1)") (class "Default")
      (node (ref "HBR4") (pin "2") (pinfunction "OUT1_2") (pintype "bidirectional"))
      (node (ref "S10") (pin "P$1") (pinfunction "0_P$1") (pintype "bidirectional"))
    )
    (net (code "25") (name "Net-(HBR4-OUT2)") (class "Default")
      (node (ref "HBR4") (pin "23") (pinfunction "OUT2_23") (pintype "bidirectional"))
      (node (ref "S10") (pin "P$2") (pinfunction "1_P$2") (pintype "bidirectional"))
    )
    (net (code "26") (name "Net-(HBR4-OUT3)") (class "Default")
      (node (ref "HBR4") (pin "14") (pinfunction "OUT3_14") (pintype "bidirectional"))
      (node (ref "S11") (pin "P$1") (pinfunction "0_P$1") (pintype "bidirectional"))
    )
    (net (code "27") (name "Net-(HBR4-OUT4)") (class "Default")
      (node (ref "HBR4") (pin "11") (pinfunction "OUT4_11") (pintype "bidirectional"))
      (node (ref "S11") (pin "P$2") (pinfunction "1_P$2") (pintype "bidirectional"))
    )
    (net (code "28") (name "Net-(HBR4-OUT5)") (class "Default")
      (node (ref "HBR4") (pin "3") (pinfunction "OUT5_3") (pintype "bidirectional"))
      (node (ref "S12") (pin "P$1") (pinfunction "0_P$1") (pintype "bidirectional"))
    )
    (net (code "29") (name "Net-(HBR4-OUT6)") (class "Default")
      (node (ref "HBR4") (pin "10") (pinfunction "OUT6_10") (pintype "bidirectional"))
      (node (ref "S12") (pin "P$2") (pinfunction "1_P$2") (pintype "bidirectional"))
    )
    (net (code "30") (name "Net-(HBR4-SO)") (class "Default")
      (node (ref "HBR4") (pin "7") (pinfunction "SO_7") (pintype "bidirectional"))
      (node (ref "HBR5") (pin "5") (pinfunction "SI_5") (pintype "bidirectional"))
    )
    (net (code "31") (name "Net-(HBR5-OUT1)") (class "Default")
      (node (ref "HBR5") (pin "2") (pinfunction "OUT1_2") (pintype "bidirectional"))
      (node (ref "S13") (pin "P$1") (pinfunction "0_P$1") (pintype "bidirectional"))
    )
    (net (code "32") (name "Net-(HBR5-OUT2)") (class "Default")
      (node (ref "HBR5") (pin "23") (pinfunction "OUT2_23") (pintype "bidirectional"))
      (node (ref "S13") (pin "P$2") (pinfunction "1_P$2") (pintype "bidirectional"))
    )
    (net (code "33") (name "Net-(HBR5-OUT3)") (class "Default")
      (node (ref "HBR5") (pin "14") (pinfunction "OUT3_14") (pintype "bidirectional"))
      (node (ref "S14") (pin "P$1") (pinfunction "0_P$1") (pintype "bidirectional"))
    )
    (net (code "34") (name "Net-(HBR5-OUT4)") (class "Default")
      (node (ref "HBR5") (pin "11") (pinfunction "OUT4_11") (pintype "bidirectional"))
      (node (ref "S14") (pin "P$2") (pinfunction "1_P$2") (pintype "bidirectional"))
    )
    (net (code "35") (name "Net-(HBR5-OUT5)") (class "Default")
      (node (ref "HBR5") (pin "3") (pinfunction "OUT5_3") (pintype "bidirectional"))
      (node (ref "S15") (pin "P$1") (pinfunction "0_P$1") (pintype "bidirectional"))
    )
    (net (code "36") (name "Net-(HBR5-OUT6)") (class "Default")
      (node (ref "HBR5") (pin "10") (pinfunction "OUT6_10") (pintype "bidirectional"))
      (node (ref "S15") (pin "P$2") (pinfunction "1_P$2") (pintype "bidirectional"))
    )
    (net (code "37") (name "Net-(HBR5-SO)") (class "Default")
      (node (ref "HBR5") (pin "7") (pinfunction "SO_7") (pintype "bidirectional"))
      (node (ref "HBR6") (pin "5") (pinfunction "SI_5") (pintype "bidirectional"))
    )
    (net (code "38") (name "Net-(HBR6-OUT1)") (class "Default")
      (node (ref "HBR6") (pin "2") (pinfunction "OUT1_2") (pintype "bidirectional"))
      (node (ref "S16") (pin "P$1") (pinfunction "0_P$1") (pintype "bidirectional"))
    )
    (net (code "39") (name "Net-(HBR6-OUT2)") (class "Default")
      (node (ref "HBR6") (pin "23") (pinfunction "OUT2_23") (pintype "bidirectional"))
      (node (ref "S16") (pin "P$2") (pinfunction "1_P$2") (pintype "bidirectional"))
    )
    (net (code "40") (name "Net-(HBR6-OUT3)") (class "Default")
      (node (ref "HBR6") (pin "14") (pinfunction "OUT3_14") (pintype "bidirectional"))
      (node (ref "S17") (pin "P$1") (pinfunction "0_P$1") (pintype "bidirectional"))
    )
    (net (code "41") (name "Net-(HBR6-OUT4)") (class "Default")
      (node (ref "HBR6") (pin "11") (pinfunction "OUT4_11") (pintype "bidirectional"))
      (node (ref "S17") (pin "P$2") (pinfunction "1_P$2") (pintype "bidirectional"))
    )
    (net (code "42") (name "Net-(HBR6-OUT5)") (class "Default")
      (node (ref "HBR6") (pin "3") (pinfunction "OUT5_3") (pintype "bidirectional"))
      (node (ref "S18") (pin "P$1") (pinfunction "0_P$1") (pintype "bidirectional"))
    )
    (net (code "43") (name "Net-(HBR6-OUT6)") (class "Default")
      (node (ref "HBR6") (pin "10") (pinfunction "OUT6_10") (pintype "bidirectional"))
      (node (ref "S18") (pin "P$2") (pinfunction "1_P$2") (pintype "bidirectional"))
    )
    (net (code "44") (name "Net-(HBR7-OUT1)") (class "Default")
      (node (ref "HBR7") (pin "2") (pinfunction "OUT1_2") (pintype "bidirectional"))
      (node (ref "S19") (pin "P$1") (pinfunction "0_P$1") (pintype "bidirectional"))
    )
    (net (code "45") (name "Net-(HBR7-OUT2)") (class "Default")
      (node (ref "HBR7") (pin "23") (pinfunction "OUT2_23") (pintype "bidirectional"))
      (node (ref "S19") (pin "P$2") (pinfunction "1_P$2") (pintype "bidirectional"))
    )
    (net (code "46") (name "Net-(HBR7-OUT3)") (class "Default")
      (node (ref "HBR7") (pin "14") (pinfunction "OUT3_14") (pintype "bidirectional"))
      (node (ref "S20") (pin "P$1") (pinfunction "0_P$1") (pintype "bidirectional"))
    )
    (net (code "47") (name "Net-(HBR7-OUT4)") (class "Default")
      (node (ref "HBR7") (pin "11") (pinfunction "OUT4_11") (pintype "bidirectional"))
      (node (ref "S20") (pin "P$2") (pinfunction "1_P$2") (pintype "bidirectional"))
    )
    (net (code "48") (name "Net-(HBR7-OUT5)") (class "Default")
      (node (ref "HBR7") (pin "3") (pinfunction "OUT5_3") (pintype "bidirectional"))
      (node (ref "S21") (pin "P$1") (pinfunction "0_P$1") (pintype "bidirectional"))
    )
    (net (code "49") (name "Net-(HBR7-OUT6)") (class "Default")
      (node (ref "HBR7") (pin "10") (pinfunction "OUT6_10") (pintype "bidirectional"))
      (node (ref "S21") (pin "P$2") (pinfunction "1_P$2") (pintype "bidirectional"))
    )
    (net (code "50") (name "Net-(HBR7-SO)") (class "Default")
      (node (ref "HBR7") (pin "7") (pinfunction "SO_7") (pintype "bidirectional"))
      (node (ref "HBR8") (pin "5") (pinfunction "SI_5") (pintype "bidirectional"))
    )
    (net (code "51") (name "Net-(HBR8-OUT1)") (class "Default")
      (node (ref "HBR8") (pin "2") (pinfunction "OUT1_2") (pintype "bidirectional"))
      (node (ref "S22") (pin "P$1") (pinfunction "0_P$1") (pintype "bidirectional"))
    )
    (net (code "52") (name "Net-(HBR8-OUT2)") (class "Default")
      (node (ref "HBR8") (pin "23") (pinfunction "OUT2_23") (pintype "bidirectional"))
      (node (ref "S22") (pin "P$2") (pinfunction "1_P$2") (pintype "bidirectional"))
    )
    (net (code "53") (name "Net-(HBR8-OUT3)") (class "Default")
      (node (ref "HBR8") (pin "14") (pinfunction "OUT3_14") (pintype "bidirectional"))
      (node (ref "S23") (pin "P$1") (pinfunction "0_P$1") (pintype "bidirectional"))
    )
    (net (code "54") (name "Net-(HBR8-OUT4)") (class "Default")
      (node (ref "HBR8") (pin "11") (pinfunction "OUT4_11") (pintype "bidirectional"))
      (node (ref "S23") (pin "P$2") (pinfunction "1_P$2") (pintype "bidirectional"))
    )
    (net (code "55") (name "Net-(HBR8-OUT5)") (class "Default")
      (node (ref "HBR8") (pin "3") (pinfunction "OUT5_3") (pintype "bidirectional"))
      (node (ref "S24") (pin "P$1") (pinfunction "0_P$1") (pintype "bidirectional"))
    )
    (net (code "56") (name "Net-(HBR8-OUT6)") (class "Default")
      (node (ref "HBR8") (pin "10") (pinfunction "OUT6_10") (pintype "bidirectional"))
      (node (ref "S24") (pin "P$2") (pinfunction "1_P$2") (pintype "bidirectional"))
    )
    (net (code "57") (name "Net-(HBR8-SO)") (class "Default")
      (node (ref "HBR8") (pin "7") (pinfunction "SO_7") (pintype "bidirectional"))
      (node (ref "HBR9") (pin "5") (pinfunction "SI_5") (pintype "bidirectional"))
    )
    (net (code "58") (name "Net-(HBR9-OUT1)") (class "Default")
      (node (ref "HBR9") (pin "2") (pinfunction "OUT1_2") (pintype "bidirectional"))
      (node (ref "S25") (pin "P$1") (pinfunction "0_P$1") (pintype "bidirectional"))
    )
    (net (code "59") (name "Net-(HBR9-OUT2)") (class "Default")
      (node (ref "HBR9") (pin "23") (pinfunction "OUT2_23") (pintype "bidirectional"))
      (node (ref "S25") (pin "P$2") (pinfunction "1_P$2") (pintype "bidirectional"))
    )
    (net (code "60") (name "Net-(HBR9-OUT3)") (class "Default")
      (node (ref "HBR9") (pin "14") (pinfunction "OUT3_14") (pintype "bidirectional"))
      (node (ref "S26") (pin "P$1") (pinfunction "0_P$1") (pintype "bidirectional"))
    )
    (net (code "61") (name "Net-(HBR9-OUT4)") (class "Default")
      (node (ref "HBR9") (pin "11") (pinfunction "OUT4_11") (pintype "bidirectional"))
      (node (ref "S26") (pin "P$2") (pinfunction "1_P$2") (pintype "bidirectional"))
    )
    (net (code "62") (name "Net-(HBR9-OUT5)") (class "Default")
      (node (ref "HBR9") (pin "3") (pinfunction "OUT5_3") (pintype "bidirectional"))
      (node (ref "S27") (pin "P$1") (pinfunction "0_P$1") (pintype "bidirectional"))
    )
    (net (code "63") (name "Net-(HBR9-OUT6)") (class "Default")
      (node (ref "HBR9") (pin "10") (pinfunction "OUT6_10") (pintype "bidirectional"))
      (node (ref "S27") (pin "P$2") (pinfunction "1_P$2") (pintype "bidirectional"))
    )
    (net (code "64") (name "Net-(HBR10-OUT1)") (class "Default")
      (node (ref "HBR10") (pin "2") (pinfunction "OUT1_2") (pintype "bidirectional"))
      (node (ref "S28") (pin "P$1") (pinfunction "0_P$1") (pintype "bidirectional"))
    )
    (net (code "65") (name "Net-(HBR10-OUT2)") (class "Default")
      (node (ref "HBR10") (pin "23") (pinfunction "OUT2_23") (pintype "bidirectional"))
      (node (ref "S28") (pin "P$2") (pinfunction "1_P$2") (pintype "bidirectional"))
    )
    (net (code "66") (name "Net-(HBR10-OUT3)") (class "Default")
      (node (ref "HBR10") (pin "14") (pinfunction "OUT3_14") (pintype "bidirectional"))
      (node (ref "S29") (pin "P$1") (pinfunction "0_P$1") (pintype "bidirectional"))
    )
    (net (code "67") (name "Net-(HBR10-OUT4)") (class "Default")
      (node (ref "HBR10") (pin "11") (pinfunction "OUT4_11") (pintype "bidirectional"))
      (node (ref "S29") (pin "P$2") (pinfunction "1_P$2") (pintype "bidirectional"))
    )
    (net (code "68") (name "Net-(HBR10-OUT5)") (class "Default")
      (node (ref "HBR10") (pin "3") (pinfunction "OUT5_3") (pintype "bidirectional"))
      (node (ref "S30") (pin "P$1") (pinfunction "0_P$1") (pintype "bidirectional"))
    )
    (net (code "69") (name "Net-(HBR10-OUT6)") (class "Default")
      (node (ref "HBR10") (pin "10") (pinfunction "OUT6_10") (pintype "bidirectional"))
      (node (ref "S30") (pin "P$2") (pinfunction "1_P$2") (pintype "bidirectional"))
    )
    (net (code "70") (name "Net-(HBR10-SO)") (class "Default")
      (node (ref "HBR10") (pin "7") (pinfunction "SO_7") (pintype "bidirectional"))
      (node (ref "HBR11") (pin "5") (pinfunction "SI_5") (pintype "bidirectional"))
    )
    (net (code "71") (name "Net-(HBR11-OUT1)") (class "Default")
      (node (ref "HBR11") (pin "2") (pinfunction "OUT1_2") (pintype "bidirectional"))
      (node (ref "S31") (pin "P$1") (pinfunction "0_P$1") (pintype "bidirectional"))
    )
    (net (code "72") (name "Net-(HBR11-OUT2)") (class "Default")
      (node (ref "HBR11") (pin "23") (pinfunction "OUT2_23") (pintype "bidirectional"))
      (node (ref "S31") (pin "P$2") (pinfunction "1_P$2") (pintype "bidirectional"))
    )
    (net (code "73") (name "Net-(HBR11-OUT3)") (class "Default")
      (node (ref "HBR11") (pin "14") (pinfunction "OUT3_14") (pintype "bidirectional"))
      (node (ref "S32") (pin "P$1") (pinfunction "0_P$1") (pintype "bidirectional"))
    )
    (net (code "74") (name "Net-(HBR11-OUT4)") (class "Default")
      (node (ref "HBR11") (pin "11") (pinfunction "OUT4_11") (pintype "bidirectional"))
      (node (ref "S32") (pin "P$2") (pinfunction "1_P$2") (pintype "bidirectional"))
    )
    (net (code "75") (name "Net-(HBR11-OUT5)") (class "Default")
      (node (ref "HBR11") (pin "3") (pinfunction "OUT5_3") (pintype "bidirectional"))
      (node (ref "S33") (pin "P$1") (pinfunction "0_P$1") (pintype "bidirectional"))
    )
    (net (code "76") (name "Net-(HBR11-OUT6)") (class "Default")
      (node (ref "HBR11") (pin "10") (pinfunction "OUT6_10") (pintype "bidirectional"))
      (node (ref "S33") (pin "P$2") (pinfunction "1_P$2") (pintype "bidirectional"))
    )
    (net (code "77") (name "Net-(HBR11-SO)") (class "Default")
      (node (ref "HBR11") (pin "7") (pinfunction "SO_7") (pintype "bidirectional"))
      (node (ref "HBR12") (pin "5") (pinfunction "SI_5") (pintype "bidirectional"))
    )
    (net (code "78") (name "Net-(HBR12-OUT1)") (class "Default")
      (node (ref "HBR12") (pin "2") (pinfunction "OUT1_2") (pintype "bidirectional"))
      (node (ref "S34") (pin "P$1") (pinfunction "0_P$1") (pintype "bidirectional"))
    )
    (net (code "79") (name "Net-(HBR12-OUT2)") (class "Default")
      (node (ref "HBR12") (pin "23") (pinfunction "OUT2_23") (pintype "bidirectional"))
      (node (ref "S34") (pin "P$2") (pinfunction "1_P$2") (pintype "bidirectional"))
    )
    (net (code "80") (name "Net-(HBR12-OUT3)") (class "Default")
      (node (ref "HBR12") (pin "14") (pinfunction "OUT3_14") (pintype "bidirectional"))
      (node (ref "S35") (pin "P$1") (pinfunction "0_P$1") (pintype "bidirectional"))
    )
    (net (code "81") (name "Net-(HBR12-OUT4)") (class "Default")
      (node (ref "HBR12") (pin "11") (pinfunction "OUT4_11") (pintype "bidirectional"))
      (node (ref "S35") (pin "P$2") (pinfunction "1_P$2") (pintype "bidirectional"))
    )
    (net (code "82") (name "Net-(HBR12-OUT5)") (class "Default")
      (node (ref "HBR12") (pin "3") (pinfunction "OUT5_3") (pintype "bidirectional"))
      (node (ref "S36") (pin "P$1") (pinfunction "0_P$1") (pintype "bidirectional"))
    )
    (net (code "83") (name "Net-(HBR12-OUT6)") (class "Default")
      (node (ref "HBR12") (pin "10") (pinfunction "OUT6_10") (pintype "bidirectional"))
      (node (ref "S36") (pin "P$2") (pinfunction "1_P$2") (pintype "bidirectional"))
    )
    (net (code "84") (name "SCK") (class "Default")
      (node (ref "HBR1") (pin "20") (pinfunction "SCLK_20") (pintype "bidirectional"))
      (node (ref "HBR10") (pin "20") (pinfunction "SCLK_20") (pintype "bidirectional"))
      (node (ref "HBR11") (pin "20") (pinfunction "SCLK_20") (pintype "bidirectional"))
      (node (ref "HBR12") (pin "20") (pinfunction "SCLK_20") (pintype "bidirectional"))
      (node (ref "HBR2") (pin "20") (pinfunction "SCLK_20") (pintype "bidirectional"))
      (node (ref "HBR3") (pin "20") (pinfunction "SCLK_20") (pintype "bidirectional"))
      (node (ref "HBR4") (pin "20") (pinfunction "SCLK_20") (pintype "bidirectional"))
      (node (ref "HBR5") (pin "20") (pinfunction "SCLK_20") (pintype "bidirectional"))
      (node (ref "HBR6") (pin "20") (pinfunction "SCLK_20") (pintype "bidirectional"))
      (node (ref "HBR7") (pin "20") (pinfunction "SCLK_20") (pintype "bidirectional"))
      (node (ref "HBR8") (pin "20") (pinfunction "SCLK_20") (pintype "bidirectional"))
      (node (ref "HBR9") (pin "20") (pinfunction "SCLK_20") (pintype "bidirectional"))
      (node (ref "IN") (pin "P$3") (pinfunction "3_P$3") (pintype "bidirectional"))
      (node (ref "OUT") (pin "P$4") (pinfunction "4_P$4") (pintype "bidirectional"))
    )
    (net (code "85") (name "SI_1") (class "Default")
      (node (ref "HBR1") (pin "5") (pinfunction "SI_5") (pintype "bidirectional"))
      (node (ref "IN") (pin "P$4") (pinfunction "4_P$4") (pintype "bidirectional"))
    )
    (net (code "86") (name "SO_1") (class "Default")
      (node (ref "HBR3") (pin "7") (pinfunction "SO_7") (pintype "bidirectional"))
      (node (ref "HBR4") (pin "5") (pinfunction "SI_5") (pintype "bidirectional"))
    )
    (net (code "87") (name "SO_2") (class "Default")
      (node (ref "HBR6") (pin "7") (pinfunction "SO_7") (pintype "bidirectional"))
      (node (ref "HBR7") (pin "5") (pinfunction "SI_5") (pintype "bidirectional"))
    )
    (net (code "88") (name "SO_3") (class "Default")
      (node (ref "HBR10") (pin "5") (pinfunction "SI_5") (pintype "bidirectional"))
      (node (ref "HBR9") (pin "7") (pinfunction "SO_7") (pintype "bidirectional"))
    )
    (net (code "89") (name "SO_4") (class "Default")
      (node (ref "HBR12") (pin "7") (pinfunction "SO_7") (pintype "bidirectional"))
      (node (ref "OUT") (pin "P$3") (pinfunction "3_P$3") (pintype "bidirectional"))
    )
    (net (code "90") (name "V+") (class "Default")
      (node (ref "HBR1") (pin "16") (pinfunction "VS2_16") (pintype "bidirectional"))
      (node (ref "HBR1") (pin "21") (pinfunction "VS1_21") (pintype "bidirectional"))
      (node (ref "HBR10") (pin "16") (pinfunction "VS2_16") (pintype "bidirectional"))
      (node (ref "HBR10") (pin "21") (pinfunction "VS1_21") (pintype "bidirectional"))
      (node (ref "HBR11") (pin "16") (pinfunction "VS2_16") (pintype "bidirectional"))
      (node (ref "HBR11") (pin "21") (pinfunction "VS1_21") (pintype "bidirectional"))
      (node (ref "HBR12") (pin "16") (pinfunction "VS2_16") (pintype "bidirectional"))
      (node (ref "HBR12") (pin "21") (pinfunction "VS1_21") (pintype "bidirectional"))
      (node (ref "HBR2") (pin "16") (pinfunction "VS2_16") (pintype "bidirectional"))
      (node (ref "HBR2") (pin "21") (pinfunction "VS1_21") (pintype "bidirectional"))
      (node (ref "HBR3") (pin "16") (pinfunction "VS2_16") (pintype "bidirectional"))
      (node (ref "HBR3") (pin "21") (pinfunction "VS1_21") (pintype "bidirectional"))
      (node (ref "HBR4") (pin "16") (pinfunction "VS2_16") (pintype "bidirectional"))
      (node (ref "HBR4") (pin "21") (pinfunction "VS1_21") (pintype "bidirectional"))
      (node (ref "HBR5") (pin "16") (pinfunction "VS2_16") (pintype "bidirectional"))
      (node (ref "HBR5") (pin "21") (pinfunction "VS1_21") (pintype "bidirectional"))
      (node (ref "HBR6") (pin "16") (pinfunction "VS2_16") (pintype "bidirectional"))
      (node (ref "HBR6") (pin "21") (pinfunction "VS1_21") (pintype "bidirectional"))
      (node (ref "HBR7") (pin "16") (pinfunction "VS2_16") (pintype "bidirectional"))
      (node (ref "HBR7") (pin "21") (pinfunction "VS1_21") (pintype "bidirectional"))
      (node (ref "HBR8") (pin "16") (pinfunction "VS2_16") (pintype "bidirectional"))
      (node (ref "HBR8") (pin "21") (pinfunction "VS1_21") (pintype "bidirectional"))
      (node (ref "HBR9") (pin "16") (pinfunction "VS2_16") (pintype "bidirectional"))
      (node (ref "HBR9") (pin "21") (pinfunction "VS1_21") (pintype "bidirectional"))
      (node (ref "IN") (pin "P$6") (pinfunction "6_P$6") (pintype "bidirectional"))
      (node (ref "OUT") (pin "P$1") (pinfunction "1_P$1") (pintype "bidirectional"))
    )
  )
)
